# Sheet2.net
KiCad netlist of a schematic drawn in Altium Designer
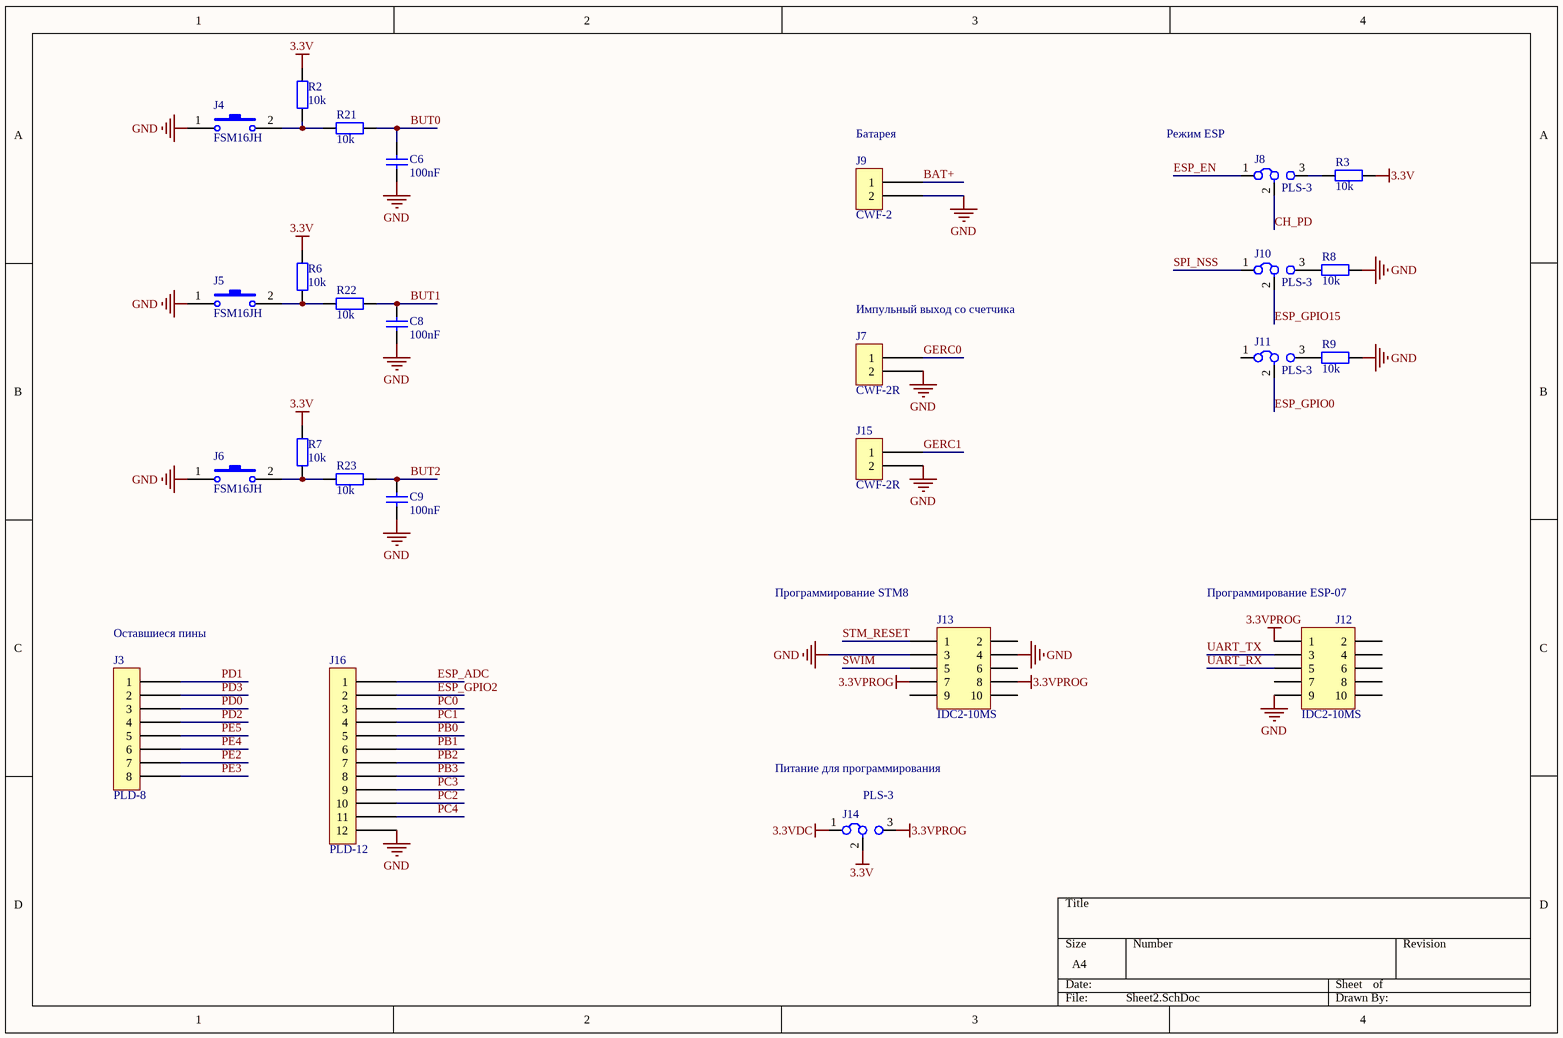
[diagram p0: Sheet2.SchDoc]

(export (version "E")
  (design (tool "Eeschema 10.0.6"))
  (components
    (comp (ref "C6")
      (value "100nF")
      (footprint "0603(CAPC1608X09N)")
      (description "Capacitor")
      (libsource (lib "Passive") (part "Capacitor"))
    )
    (comp (ref "C8")
      (value "100nF")
      (footprint "0603(CAPC1608X09N)")
      (description "Capacitor")
      (libsource (lib "Passive") (part "Capacitor"))
    )
    (comp (ref "C9")
      (value "100nF")
      (footprint "0603(CAPC1608X09N)")
      (description "Capacitor")
      (libsource (lib "Passive") (part "Capacitor"))
    )
    (comp (ref "J3")
      (value "PLD-8")
      (footprint "PLD-8")
      (description "Вилка штыревая PLD-8, прямая")
      (fields (field (name "MANUFACTURER") "Connfly"))
      (libsource (lib "Schlib1") (part "PLD-8"))
    )
    (comp (ref "J4")
      (value "FSM16JH")
      (footprint "FSM16JH")
      (description "Tact switch")
      (libsource (lib "Schlib1") (part "Tact switch"))
    )
    (comp (ref "J5")
      (value "FSM16JH")
      (footprint "FSM16JH")
      (description "Tact switch")
      (libsource (lib "Schlib1") (part "Tact switch"))
    )
    (comp (ref "J6")
      (value "FSM16JH")
      (footprint "FSM16JH")
      (description "Tact switch")
      (libsource (lib "Schlib1") (part "Tact switch"))
    )
    (comp (ref "J7")
      (value "CWF-2R")
      (footprint "DS1069-2MRW6XB")
      (description "Вилка на плату CWF-2R, угловая")
      (fields (field (name "MANUFACTURER") "Connfly") (field (name "PART NUMBER") "DS1069-2MRW6XB"))
      (libsource (lib "Schlib1") (part "CWF-2R"))
    )
    (comp (ref "J8")
      (value "PLS-3")
      (footprint "PLS-3")
      (description "Вилка штыревая PLS-3, прямая")
      (libsource (lib "Connectors") (part "PLS-3"))
    )
    (comp (ref "J9")
      (value "CWF-2")
      (footprint "DS1069-2MVW6X")
      (description "Вилка на плату CWF-2, прямая")
      (fields (field (name "MANUFACTURER") "Connfly") (field (name "PART NUMBER") "DS1069-2MVW6X"))
      (libsource (lib "Schlib1") (part "CWF-2"))
    )
    (comp (ref "J10")
      (value "PLS-3")
      (footprint "PLS-3")
      (description "Вилка штыревая PLS-3, прямая")
      (libsource (lib "Connectors") (part "PLS-3"))
    )
    (comp (ref "J11")
      (value "PLS-3")
      (footprint "PLS-3")
      (description "Вилка штыревая PLS-3, прямая")
      (libsource (lib "Connectors") (part "PLS-3"))
    )
    (comp (ref "J12")
      (value "IDC2-10MS")
      (footprint "IDC2-10MS")
      (description "Вилка на плату IDC2-10MS, прямая")
      (libsource (lib "Connectors") (part "IDC2-10MS"))
    )
    (comp (ref "J13")
      (value "IDC2-10MS")
      (footprint "IDC2-10MS")
      (description "Вилка на плату IDC2-10MS, прямая")
      (libsource (lib "Connectors") (part "IDC2-10MS"))
    )
    (comp (ref "J14")
      (value "PLS-3")
      (footprint "PLS-3")
      (description "Вилка штыревая PLS-3, прямая")
      (libsource (lib "Connectors") (part "PLS-3"))
    )
    (comp (ref "J15")
      (value "CWF-2R")
      (footprint "DS1069-2MRW6XB")
      (description "Вилка на плату CWF-2R, угловая")
      (fields (field (name "MANUFACTURER") "Connfly") (field (name "PART NUMBER") "DS1069-2MRW6XB"))
      (libsource (lib "Schlib1") (part "CWF-2R"))
    )
    (comp (ref "J16")
      (value "PLD-12")
      (footprint "PLD-12")
      (description "Вилка штыревая PLD-12, прямая")
      (fields (field (name "MANUFACTURER") "Connfly"))
      (libsource (lib "Schlib1") (part "PLD-12"))
    )
    (comp (ref "R2")
      (value "10k")
      (footprint "0603(RESC1608X05N)")
      (description "Resistor")
      (libsource (lib "") (part "Resistor_1"))
    )
    (comp (ref "R3")
      (value "10k")
      (footprint "0603(RESC1608X05N)")
      (description "Resistor")
      (libsource (lib "Passive") (part "Resistor"))
    )
    (comp (ref "R6")
      (value "10k")
      (footprint "0603(RESC1608X05N)")
      (description "Resistor")
      (libsource (lib "") (part "Resistor_1"))
    )
    (comp (ref "R7")
      (value "10k")
      (footprint "0603(RESC1608X05N)")
      (description "Resistor")
      (libsource (lib "") (part "Resistor_1"))
    )
    (comp (ref "R8")
      (value "10k")
      (footprint "0603(RESC1608X05N)")
      (description "Resistor")
      (libsource (lib "Passive") (part "Resistor"))
    )
    (comp (ref "R9")
      (value "10k")
      (footprint "0603(RESC1608X05N)")
      (description "Resistor")
      (libsource (lib "Passive") (part "Resistor"))
    )
    (comp (ref "R21")
      (value "10k")
      (footprint "0603(RESC1608X05N)")
      (description "Resistor")
      (libsource (lib "Passive") (part "Resistor"))
    )
    (comp (ref "R22")
      (value "10k")
      (footprint "0603(RESC1608X05N)")
      (description "Resistor")
      (libsource (lib "Passive") (part "Resistor"))
    )
    (comp (ref "R23")
      (value "10k")
      (footprint "0603(RESC1608X05N)")
      (description "Resistor")
      (libsource (lib "Passive") (part "Resistor"))
    )
  )
  (nets
    (net (code "1") (name "/BAT+") (class "Default")
      (node (ref "J9") (pin "1") (pinfunction "1_1") (pintype "passive"))
    )
    (net (code "2") (name "/BUT0") (class "Default")
      (node (ref "C6") (pin "2") (pinfunction "2_2") (pintype "passive"))
      (node (ref "R21") (pin "2") (pinfunction "2_2") (pintype "passive"))
    )
    (net (code "3") (name "/BUT1") (class "Default")
      (node (ref "C8") (pin "2") (pinfunction "2_2") (pintype "passive"))
      (node (ref "R22") (pin "2") (pinfunction "2_2") (pintype "passive"))
    )
    (net (code "4") (name "/BUT2") (class "Default")
      (node (ref "C9") (pin "2") (pinfunction "2_2") (pintype "passive"))
      (node (ref "R23") (pin "2") (pinfunction "2_2") (pintype "passive"))
    )
    (net (code "5") (name "/CH_PD") (class "Default")
      (node (ref "J8") (pin "2") (pinfunction "2_2") (pintype "passive"))
    )
    (net (code "6") (name "/ESP_ADC") (class "Default")
      (node (ref "J16") (pin "1") (pinfunction "1_1") (pintype "passive"))
    )
    (net (code "7") (name "/ESP_EN") (class "Default")
      (node (ref "J8") (pin "1") (pinfunction "1_1") (pintype "passive"))
    )
    (net (code "8") (name "/ESP_GPIO0") (class "Default")
      (node (ref "J11") (pin "2") (pinfunction "2_2") (pintype "passive"))
    )
    (net (code "9") (name "/ESP_GPIO2") (class "Default")
      (node (ref "J16") (pin "2") (pinfunction "2_2") (pintype "passive"))
    )
    (net (code "10") (name "/ESP_GPIO15") (class "Default")
      (node (ref "J10") (pin "2") (pinfunction "2_2") (pintype "passive"))
    )
    (net (code "11") (name "/GERC0") (class "Default")
      (node (ref "J7") (pin "1") (pinfunction "1_1") (pintype "passive"))
    )
    (net (code "12") (name "/GERC1") (class "Default")
      (node (ref "J15") (pin "1") (pinfunction "1_1") (pintype "passive"))
    )
    (net (code "13") (name "/PB0") (class "Default")
      (node (ref "J16") (pin "5") (pinfunction "5_5") (pintype "passive"))
    )
    (net (code "14") (name "/PB1") (class "Default")
      (node (ref "J16") (pin "6") (pinfunction "6_6") (pintype "passive"))
    )
    (net (code "15") (name "/PB2") (class "Default")
      (node (ref "J16") (pin "7") (pinfunction "7_7") (pintype "passive"))
    )
    (net (code "16") (name "/PB3") (class "Default")
      (node (ref "J16") (pin "8") (pinfunction "8_8") (pintype "passive"))
    )
    (net (code "17") (name "/PC0") (class "Default")
      (node (ref "J16") (pin "3") (pinfunction "3_3") (pintype "passive"))
    )
    (net (code "18") (name "/PC1") (class "Default")
      (node (ref "J16") (pin "4") (pinfunction "4_4") (pintype "passive"))
    )
    (net (code "19") (name "/PC2") (class "Default")
      (node (ref "J16") (pin "10") (pinfunction "10_10") (pintype "passive"))
    )
    (net (code "20") (name "/PC3") (class "Default")
      (node (ref "J16") (pin "9") (pinfunction "9_9") (pintype "passive"))
    )
    (net (code "21") (name "/PC4") (class "Default")
      (node (ref "J16") (pin "11") (pinfunction "11_11") (pintype "passive"))
    )
    (net (code "22") (name "/PD0") (class "Default")
      (node (ref "J3") (pin "3") (pinfunction "3_3") (pintype "passive"))
    )
    (net (code "23") (name "/PD1") (class "Default")
      (node (ref "J3") (pin "1") (pinfunction "1_1") (pintype "passive"))
    )
    (net (code "24") (name "/PD2") (class "Default")
      (node (ref "J3") (pin "4") (pinfunction "4_4") (pintype "passive"))
    )
    (net (code "25") (name "/PD3") (class "Default")
      (node (ref "J3") (pin "2") (pinfunction "2_2") (pintype "passive"))
    )
    (net (code "26") (name "/PE2") (class "Default")
      (node (ref "J3") (pin "7") (pinfunction "7_7") (pintype "passive"))
    )
    (net (code "27") (name "/PE3") (class "Default")
      (node (ref "J3") (pin "8") (pinfunction "8_8") (pintype "passive"))
    )
    (net (code "28") (name "/PE4") (class "Default")
      (node (ref "J3") (pin "6") (pinfunction "6_6") (pintype "passive"))
    )
    (net (code "29") (name "/PE5") (class "Default")
      (node (ref "J3") (pin "5") (pinfunction "5_5") (pintype "passive"))
    )
    (net (code "30") (name "/SPI_NSS") (class "Default")
      (node (ref "J10") (pin "1") (pinfunction "1_1") (pintype "passive"))
    )
    (net (code "31") (name "/STM_RESET") (class "Default")
      (node (ref "J13") (pin "1") (pinfunction "1_1") (pintype "passive"))
    )
    (net (code "32") (name "/SWIM") (class "Default")
      (node (ref "J13") (pin "5") (pinfunction "5_5") (pintype "passive"))
    )
    (net (code "33") (name "/UART_RX") (class "Default")
      (node (ref "J12") (pin "5") (pinfunction "5_5") (pintype "passive"))
    )
    (net (code "34") (name "/UART_TX") (class "Default")
      (node (ref "J12") (pin "3") (pinfunction "3_3") (pintype "passive"))
    )
    (net (code "35") (name "3.3V") (class "Default")
      (node (ref "J14") (pin "2") (pinfunction "2_2") (pintype "passive"))
      (node (ref "R2") (pin "2") (pinfunction "2_2") (pintype "passive"))
      (node (ref "R3") (pin "2") (pinfunction "2_2") (pintype "passive"))
      (node (ref "R6") (pin "2") (pinfunction "2_2") (pintype "passive"))
      (node (ref "R7") (pin "2") (pinfunction "2_2") (pintype "passive"))
    )
    (net (code "36") (name "3.3VDC") (class "Default")
      (node (ref "J14") (pin "1") (pinfunction "1_1") (pintype "passive"))
    )
    (net (code "37") (name "3.3VPROG") (class "Default")
      (node (ref "J12") (pin "1") (pinfunction "1_1") (pintype "passive"))
      (node (ref "J13") (pin "7") (pinfunction "7_7") (pintype "passive"))
      (node (ref "J13") (pin "8") (pinfunction "8_8") (pintype "passive"))
      (node (ref "J14") (pin "3") (pinfunction "3_3") (pintype "passive"))
    )
    (net (code "38") (name "GND") (class "Default")
      (node (ref "C6") (pin "1") (pinfunction "1_1") (pintype "passive"))
      (node (ref "C8") (pin "1") (pinfunction "1_1") (pintype "passive"))
      (node (ref "C9") (pin "1") (pinfunction "1_1") (pintype "passive"))
      (node (ref "J12") (pin "9") (pinfunction "9_9") (pintype "passive"))
      (node (ref "J13") (pin "3") (pinfunction "3_3") (pintype "passive"))
      (node (ref "J13") (pin "4") (pinfunction "4_4") (pintype "passive"))
      (node (ref "J15") (pin "2") (pinfunction "2_2") (pintype "passive"))
      (node (ref "J16") (pin "12") (pinfunction "12_12") (pintype "passive"))
      (node (ref "J4") (pin "1") (pinfunction "COMMON1_1") (pintype "passive"))
      (node (ref "J5") (pin "1") (pinfunction "COMMON1_1") (pintype "passive"))
      (node (ref "J6") (pin "1") (pinfunction "COMMON1_1") (pintype "passive"))
      (node (ref "J7") (pin "2") (pinfunction "2_2") (pintype "passive"))
      (node (ref "J9") (pin "2") (pinfunction "2_2") (pintype "passive"))
      (node (ref "R8") (pin "2") (pinfunction "2_2") (pintype "passive"))
      (node (ref "R9") (pin "2") (pinfunction "2_2") (pintype "passive"))
    )
    (net (code "39") (name "Net-(J4-NO1)") (class "Default")
      (node (ref "J4") (pin "2") (pinfunction "NO1_2") (pintype "passive"))
      (node (ref "R2") (pin "1") (pinfunction "1_1") (pintype "passive"))
      (node (ref "R21") (pin "1") (pinfunction "1_1") (pintype "passive"))
    )
    (net (code "40") (name "Net-(J5-NO1)") (class "Default")
      (node (ref "J5") (pin "2") (pinfunction "NO1_2") (pintype "passive"))
      (node (ref "R22") (pin "1") (pinfunction "1_1") (pintype "passive"))
      (node (ref "R6") (pin "1") (pinfunction "1_1") (pintype "passive"))
    )
    (net (code "41") (name "Net-(J6-NO1)") (class "Default")
      (node (ref "J6") (pin "2") (pinfunction "NO1_2") (pintype "passive"))
      (node (ref "R23") (pin "1") (pinfunction "1_1") (pintype "passive"))
      (node (ref "R7") (pin "1") (pinfunction "1_1") (pintype "passive"))
    )
    (net (code "42") (name "Net-(J8-Pad3)") (class "Default")
      (node (ref "J8") (pin "3") (pinfunction "3_3") (pintype "passive"))
      (node (ref "R3") (pin "1") (pinfunction "1_1") (pintype "passive"))
    )
    (net (code "43") (name "Net-(J10-Pad3)") (class "Default")
      (node (ref "J10") (pin "3") (pinfunction "3_3") (pintype "passive"))
      (node (ref "R8") (pin "1") (pinfunction "1_1") (pintype "passive"))
    )
    (net (code "44") (name "Net-(J11-Pad3)") (class "Default")
      (node (ref "J11") (pin "3") (pinfunction "3_3") (pintype "passive"))
      (node (ref "R9") (pin "1") (pinfunction "1_1") (pintype "passive"))
    )
    (net (code "45") (name "unconnected-(J11-Pad1)") (class "Default")
      (node (ref "J11") (pin "1") (pinfunction "1_1") (pintype "passive"))
    )
    (net (code "46") (name "unconnected-(J12-Pad2)") (class "Default")
      (node (ref "J12") (pin "2") (pinfunction "2_2") (pintype "passive"))
    )
    (net (code "47") (name "unconnected-(J12-Pad4)") (class "Default")
      (node (ref "J12") (pin "4") (pinfunction "4_4") (pintype "passive"))
    )
    (net (code "48") (name "unconnected-(J12-Pad6)") (class "Default")
      (node (ref "J12") (pin "6") (pinfunction "6_6") (pintype "passive"))
    )
    (net (code "49") (name "unconnected-(J12-Pad7)") (class "Default")
      (node (ref "J12") (pin "7") (pinfunction "7_7") (pintype "passive"))
    )
    (net (code "50") (name "unconnected-(J12-Pad8)") (class "Default")
      (node (ref "J12") (pin "8") (pinfunction "8_8") (pintype "passive"))
    )
    (net (code "51") (name "unconnected-(J12-Pad10)") (class "Default")
      (node (ref "J12") (pin "10") (pinfunction "10_10") (pintype "passive"))
    )
    (net (code "52") (name "unconnected-(J13-Pad2)") (class "Default")
      (node (ref "J13") (pin "2") (pinfunction "2_2") (pintype "passive"))
    )
    (net (code "53") (name "unconnected-(J13-Pad6)") (class "Default")
      (node (ref "J13") (pin "6") (pinfunction "6_6") (pintype "passive"))
    )
    (net (code "54") (name "unconnected-(J13-Pad9)") (class "Default")
      (node (ref "J13") (pin "9") (pinfunction "9_9") (pintype "passive"))
    )
    (net (code "55") (name "unconnected-(J13-Pad10)") (class "Default")
      (node (ref "J13") (pin "10") (pinfunction "10_10") (pintype "passive"))
    )
  )
)
